# Schematics.net
KiCad netlist of a schematic drawn in Altium Designer
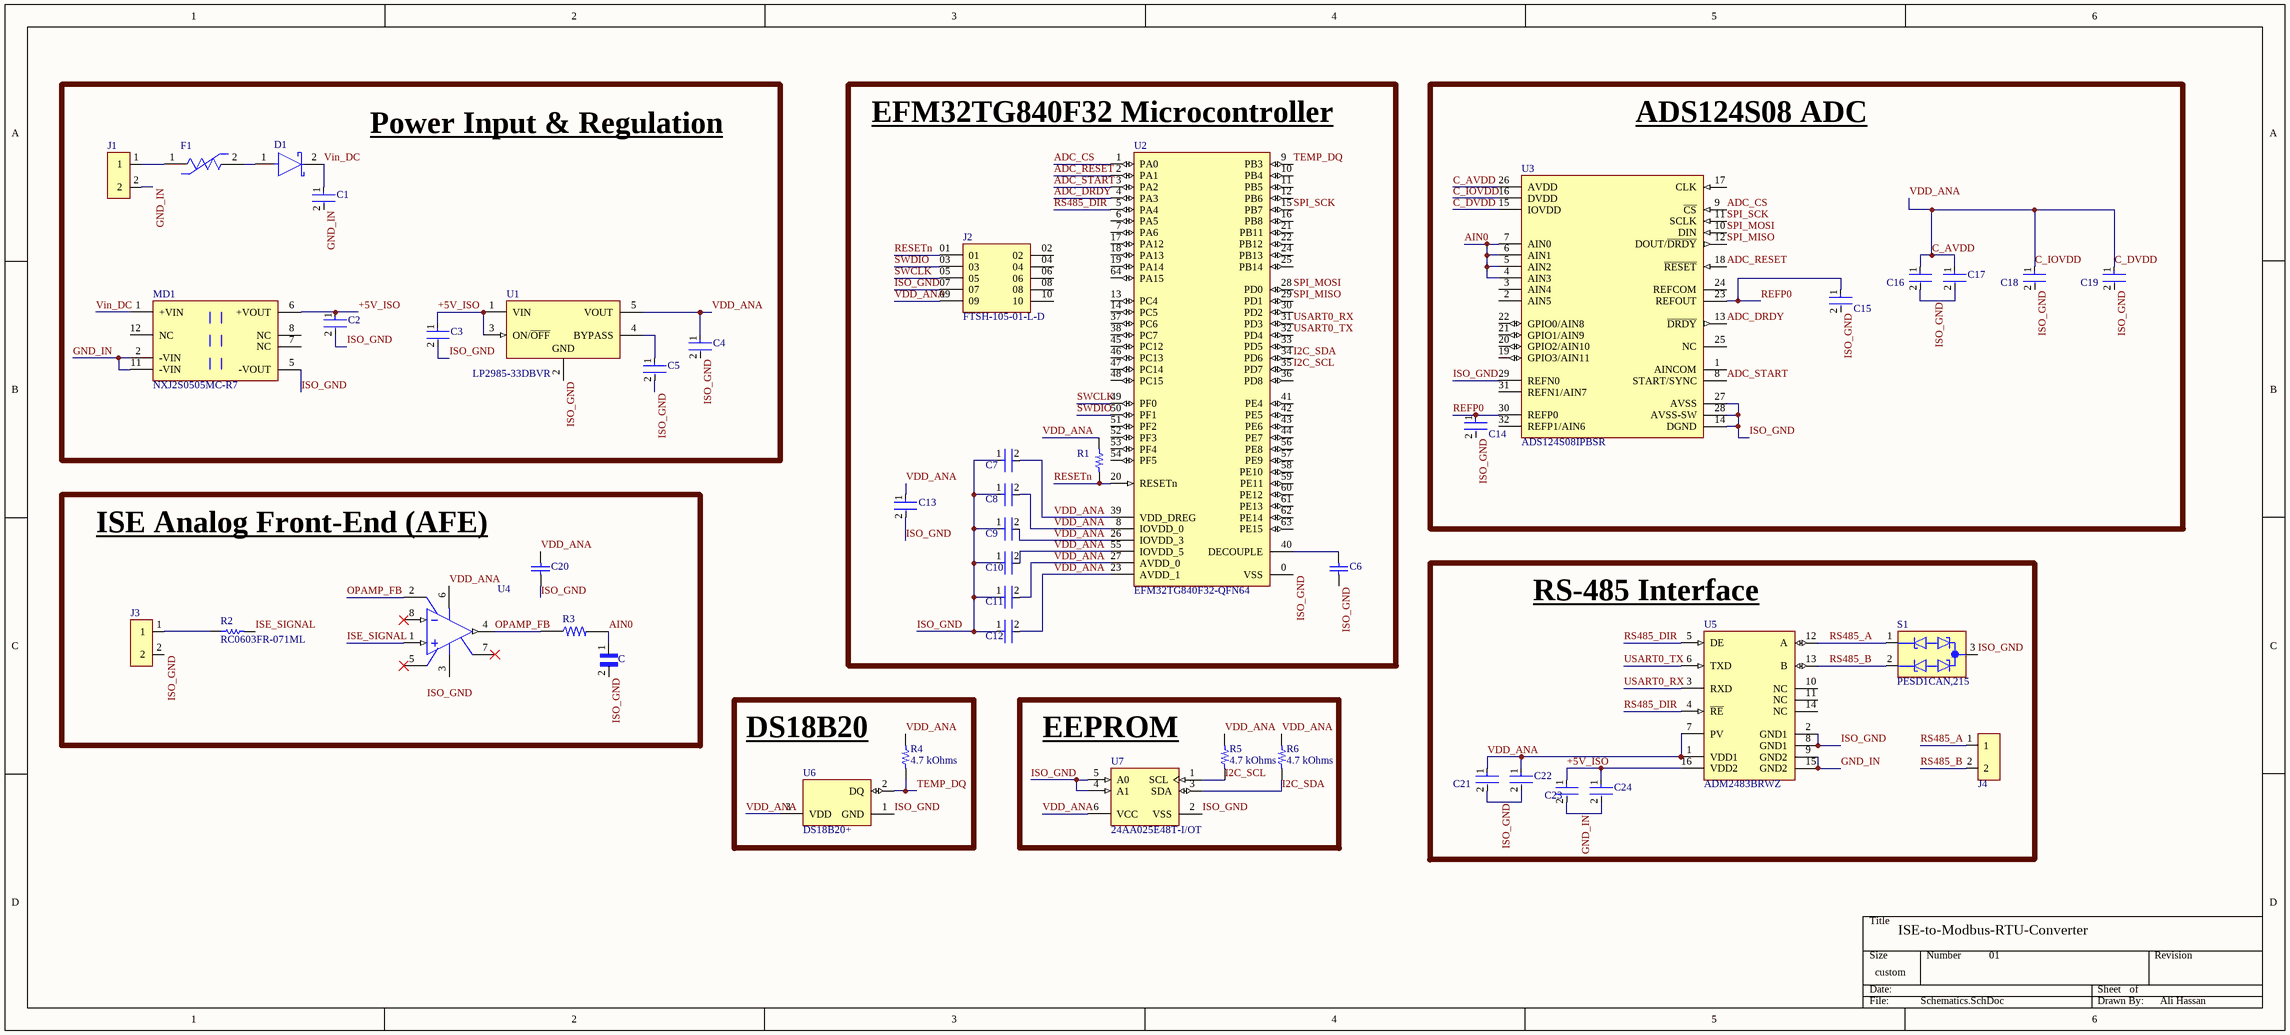
[diagram p0: Schematics.SchDoc]

(export (version "E")
  (design (tool "Eeschema 10.0.6"))
  (components
    (comp (ref "C")
      (value "CL10B104KO8NNNC")
      (footprint "CAPC1608X90N")
      (description "0.1ÂµF Â±10% 16V Ceramic Capacitor X7R 0603 _1608 Metric_")
      (fields (field (name "MF") "Samsung Electro-Mechanics"))
      (libsource (lib "CL10B104KO8NNNC") (part "CL10B104KO8NNNC"))
    )
    (comp (ref "C1")
      (value "GRM188R60J106ME47D")
      (footprint "FP-GRM188-0_1-e0_2_0_55-IPC_A")
      (description "Chip Multilayer Ceramic Capacitors for General Purpose, 0603, 10uF, X5R, 15%, 20%, 6.3V")
      (fields (field (name "VOLTAGE") "6.3V") (field (name "TOLERANCE") "20%"))
      (libsource (lib "Altium Content Vault") (part "02cd4be3c70576c341d710602a673aa"))
    )
    (comp (ref "C2")
      (value "GRM188R60J106ME47D")
      (footprint "FP-GRM188-0_1-e0_2_0_55-IPC_A")
      (description "Chip Multilayer Ceramic Capacitors for General Purpose, 0603, 10uF, X5R, 15%, 20%, 6.3V")
      (fields (field (name "VOLTAGE") "6.3V") (field (name "TOLERANCE") "20%"))
      (libsource (lib "Altium Content Vault") (part "02cd4be3c70576c341d710602a673aa"))
    )
    (comp (ref "C3")
      (value "GRM188R60J106ME47D")
      (footprint "FP-GRM188-0_1-e0_2_0_55-IPC_A")
      (description "Chip Multilayer Ceramic Capacitors for General Purpose, 0603, 10uF, X5R, 15%, 20%, 6.3V")
      (fields (field (name "VOLTAGE") "6.3V") (field (name "TOLERANCE") "20%"))
      (libsource (lib "Altium Content Vault") (part "02cd4be3c70576c341d710602a673aa"))
    )
    (comp (ref "C4")
      (value "GRM188R60J106ME47D")
      (footprint "FP-GRM188-0_1-e0_2_0_55-IPC_A")
      (description "Chip Multilayer Ceramic Capacitors for General Purpose, 0603, 10uF, X5R, 15%, 20%, 6.3V")
      (fields (field (name "VOLTAGE") "6.3V") (field (name "TOLERANCE") "20%"))
      (libsource (lib "Altium Content Vault") (part "02cd4be3c70576c341d710602a673aa"))
    )
    (comp (ref "C5")
      (value "GRM188R60J106ME47D")
      (footprint "FP-GRM188-0_1-e0_2_0_55-IPC_A")
      (description "Chip Multilayer Ceramic Capacitors for General Purpose, 0603, 10uF, X5R, 15%, 20%, 6.3V")
      (fields (field (name "VOLTAGE") "6.3V") (field (name "TOLERANCE") "20%"))
      (libsource (lib "Altium Content Vault") (part "02cd4be3c70576c341d710602a673aa"))
    )
    (comp (ref "C6")
      (value "C0805C105K4PACTU")
      (footprint "CAPC2013X145X50LL20T25")
      (fields (field (name "MANUFACTURER") "Kemet"))
      (libsource (lib "Altium Content Vault") (part "CAP"))
    )
    (comp (ref "C7")
      (value "C1005X7R1H104K050BB")
      (footprint "FP-C1005-050-0_05-IPC_C")
      (description "Multilayer Ceramic Capacitors 100nF ±10% 50V X7R SMD 0402")
      (fields (field (name "VOLTAGE") "50V") (field (name "TOLERANCE") "10%"))
      (libsource (lib "Altium Content Vault") (part "b4654b650e69147ec39a6b967a45e02"))
    )
    (comp (ref "C8")
      (value "C1005X7R1H104K050BB")
      (footprint "FP-C1005-050-0_05-IPC_C")
      (description "Multilayer Ceramic Capacitors 100nF ±10% 50V X7R SMD 0402")
      (fields (field (name "VOLTAGE") "50V") (field (name "TOLERANCE") "10%"))
      (libsource (lib "Altium Content Vault") (part "b4654b650e69147ec39a6b967a45e02"))
    )
    (comp (ref "C9")
      (value "C1005X7R1H104K050BB")
      (footprint "FP-C1005-050-0_05-IPC_C")
      (description "Multilayer Ceramic Capacitors 100nF ±10% 50V X7R SMD 0402")
      (fields (field (name "VOLTAGE") "50V") (field (name "TOLERANCE") "10%"))
      (libsource (lib "Altium Content Vault") (part "b4654b650e69147ec39a6b967a45e02"))
    )
    (comp (ref "C10")
      (value "C1005X7R1H104K050BB")
      (footprint "FP-C1005-050-0_05-IPC_C")
      (description "Multilayer Ceramic Capacitors 100nF ±10% 50V X7R SMD 0402")
      (fields (field (name "VOLTAGE") "50V") (field (name "TOLERANCE") "10%"))
      (libsource (lib "Altium Content Vault") (part "b4654b650e69147ec39a6b967a45e02"))
    )
    (comp (ref "C11")
      (value "C1005X7R1H104K050BB")
      (footprint "FP-C1005-050-0_05-IPC_C")
      (description "Multilayer Ceramic Capacitors 100nF ±10% 50V X7R SMD 0402")
      (fields (field (name "VOLTAGE") "50V") (field (name "TOLERANCE") "10%"))
      (libsource (lib "Altium Content Vault") (part "b4654b650e69147ec39a6b967a45e02"))
    )
    (comp (ref "C12")
      (value "C1005X7R1H104K050BB")
      (footprint "FP-C1005-050-0_05-IPC_C")
      (description "Multilayer Ceramic Capacitors 100nF ±10% 50V X7R SMD 0402")
      (fields (field (name "VOLTAGE") "50V") (field (name "TOLERANCE") "10%"))
      (libsource (lib "Altium Content Vault") (part "b4654b650e69147ec39a6b967a45e02"))
    )
    (comp (ref "C13")
      (value "GRM188R60J106ME47D")
      (footprint "FP-GRM188-0_1-e0_2_0_55-IPC_A")
      (description "Chip Multilayer Ceramic Capacitors for General Purpose, 0603, 10uF, X5R, 15%, 20%, 6.3V")
      (fields (field (name "VOLTAGE") "6.3V") (field (name "TOLERANCE") "20%"))
      (libsource (lib "Altium Content Vault") (part "02cd4be3c70576c341d710602a673aa"))
    )
    (comp (ref "C14")
      (value "C1005X7R1H104K050BB")
      (footprint "FP-C1005-050-0_05-IPC_C")
      (description "Multilayer Ceramic Capacitors 100nF ±10% 50V X7R SMD 0402")
      (fields (field (name "VOLTAGE") "50V") (field (name "TOLERANCE") "10%"))
      (libsource (lib "Altium Content Vault") (part "b4654b650e69147ec39a6b967a45e02"))
    )
    (comp (ref "C15")
      (value "C1005X7R1H104K050BB")
      (footprint "FP-C1005-050-0_05-IPC_C")
      (description "Multilayer Ceramic Capacitors 100nF ±10% 50V X7R SMD 0402")
      (fields (field (name "VOLTAGE") "50V") (field (name "TOLERANCE") "10%"))
      (libsource (lib "Altium Content Vault") (part "b4654b650e69147ec39a6b967a45e02"))
    )
    (comp (ref "C16")
      (value "C1005X7R1H104K050BB")
      (footprint "FP-C1005-050-0_05-IPC_C")
      (description "Multilayer Ceramic Capacitors 100nF ±10% 50V X7R SMD 0402")
      (fields (field (name "VOLTAGE") "50V") (field (name "TOLERANCE") "10%"))
      (libsource (lib "Altium Content Vault") (part "b4654b650e69147ec39a6b967a45e02"))
    )
    (comp (ref "C17")
      (value "GRM188R60J106ME47D")
      (footprint "FP-GRM188-0_1-e0_2_0_55-IPC_A")
      (description "Chip Multilayer Ceramic Capacitors for General Purpose, 0603, 10uF, X5R, 15%, 20%, 6.3V")
      (fields (field (name "VOLTAGE") "6.3V") (field (name "TOLERANCE") "20%"))
      (libsource (lib "Altium Content Vault") (part "02cd4be3c70576c341d710602a673aa"))
    )
    (comp (ref "C18")
      (value "C1005X7R1H104K050BB")
      (footprint "FP-C1005-050-0_05-IPC_C")
      (description "Multilayer Ceramic Capacitors 100nF ±10% 50V X7R SMD 0402")
      (fields (field (name "VOLTAGE") "50V") (field (name "TOLERANCE") "10%"))
      (libsource (lib "Altium Content Vault") (part "b4654b650e69147ec39a6b967a45e02"))
    )
    (comp (ref "C19")
      (value "C1005X7R1H104K050BB")
      (footprint "FP-C1005-050-0_05-IPC_C")
      (description "Multilayer Ceramic Capacitors 100nF ±10% 50V X7R SMD 0402")
      (fields (field (name "VOLTAGE") "50V") (field (name "TOLERANCE") "10%"))
      (libsource (lib "Altium Content Vault") (part "b4654b650e69147ec39a6b967a45e02"))
    )
    (comp (ref "C20")
      (value "GRM188R71C104KA01D")
      (footprint "MURA-0603_H_0.9_M")
      (description "CAP, Ceramic, 0.1 uF, 10%, 16 V, 0603, RoHS, Tape and Reel")
      (fields (field (name "MANUFACTURER") "Murata") (field (name "TOLERANCE") "10%"))
      (libsource (lib "Altium Content Vault") (part "CAP-NP-2"))
    )
    (comp (ref "C21")
      (value "C1005X7R1H104K050BB")
      (footprint "FP-C1005-050-0_05-IPC_C")
      (description "Multilayer Ceramic Capacitors 100nF ±10% 50V X7R SMD 0402")
      (fields (field (name "VOLTAGE") "50V") (field (name "TOLERANCE") "10%"))
      (libsource (lib "Altium Content Vault") (part "b4654b650e69147ec39a6b967a45e02"))
    )
    (comp (ref "C22")
      (value "GRM188R60J106ME47D")
      (footprint "FP-GRM188-0_1-e0_2_0_55-IPC_A")
      (description "Chip Multilayer Ceramic Capacitors for General Purpose, 0603, 10uF, X5R, 15%, 20%, 6.3V")
      (fields (field (name "VOLTAGE") "6.3V") (field (name "TOLERANCE") "20%"))
      (libsource (lib "Altium Content Vault") (part "02cd4be3c70576c341d710602a673aa"))
    )
    (comp (ref "C23")
      (value "C1005X7R1H104K050BB")
      (footprint "FP-C1005-050-0_05-IPC_C")
      (description "Multilayer Ceramic Capacitors 100nF ±10% 50V X7R SMD 0402")
      (fields (field (name "VOLTAGE") "50V") (field (name "TOLERANCE") "10%"))
      (libsource (lib "Altium Content Vault") (part "b4654b650e69147ec39a6b967a45e02"))
    )
    (comp (ref "C24")
      (value "GRM188R60J106ME47D")
      (footprint "FP-GRM188-0_1-e0_2_0_55-IPC_A")
      (description "Chip Multilayer Ceramic Capacitors for General Purpose, 0603, 10uF, X5R, 15%, 20%, 6.3V")
      (fields (field (name "VOLTAGE") "6.3V") (field (name "TOLERANCE") "20%"))
      (libsource (lib "Altium Content Vault") (part "02cd4be3c70576c341d710602a673aa"))
    )
    (comp (ref "D1")
      (value "SS14")
      (footprint "FP-403AE-MFG")
      (description "DIODE SCHOTTKY 40V 1A SMA")
      (fields
        (field (name "MANUFACTURER") "ON Semiconductor")
        (field (name "OCTOPART") "https://octopart.com/ss14-on+semiconductor-29205033")
      )
      (libsource (lib "Altium Content Vault") (part "360ad2f4ac25a952324d13796385471"))
    )
    (comp (ref "F1")
      (value "1206L050YR")
      (footprint "FP-1206L050YR-MFG")
      (description "PTC RESET FUSE 6V 500MA 1206")
      (libsource (lib "Altium Content Vault") (part "fdf083d5f6389a9a1c4e51137f46658"))
    )
    (comp (ref "J1")
      (value "OSTTC020162")
      (footprint "OST_OSTTC020162")
      (description "2 Position Wire to Board Terminal Block Horizontal with Board 0.197 _5.00mm_ Through Hole")
      (fields (field (name "MF") "On Shore"))
      (libsource (lib "OSTTC020162") (part "OSTTC020162"))
    )
    (comp (ref "J2")
      (value "FTSH-105-01-L-D")
      (footprint "SAMTEC_FTSH-105-01-L-D")
      (fields (field (name "MF") "Samtec"))
      (libsource (lib "FTSH-105-01-L-D") (part "FTSH-105-01-L-D"))
    )
    (comp (ref "J3")
      (value "OSTTC020162")
      (footprint "OST_OSTTC020162")
      (description "2 Position Wire to Board Terminal Block Horizontal with Board 0.197 _5.00mm_ Through Hole")
      (fields (field (name "MF") "On Shore"))
      (libsource (lib "OSTTC020162") (part "OSTTC020162"))
    )
    (comp (ref "J4")
      (value "OSTTC020162")
      (footprint "OST_OSTTC020162")
      (description "2 Position Wire to Board Terminal Block Horizontal with Board 0.197 _5.00mm_ Through Hole")
      (fields (field (name "MF") "On Shore"))
      (libsource (lib "") (part "OSTTC020162_1"))
    )
    (comp (ref "MD1")
      (value "NXJ2S0505MC-R7")
      (footprint "FP-NXJ2SM-MFG")
      (description "DC DC CONVERTER 5V 2W")
      (libsource (lib "Altium Content Vault") (part "702c7546206b672000c29661061961a"))
    )
    (comp (ref "R1")
      (value "10 kOhms")
      (footprint "YAGEO RES 0603_1608")
      (description "RES SMD 10K OHM 1% 1/10W 0603")
      (fields (field (name "PART NUMBER") "AA0603FR-0710KL") (field (name "MANUFACTURER") "Yageo"))
      (libsource (lib "Celestial Altium Library - altium_library") (part "Resistor"))
    )
    (comp (ref "R2")
      (value "RC0603FR-071ML")
      (footprint "RESC1608X55X25LL10T15")
      (description "Chip Resistor, 1 MOhm, +/- 1%, 100 mW, -55 to 155 degC, 0603 (1608 Metric), RoHS, Tape and Reel")
      (fields (field (name "TOLERANCE") "20%"))
      (libsource (lib "Altium Content Vault") (part "RES-2"))
    )
    (comp (ref "R3")
      (value "RC0603FR-07100RL")
      (footprint "RESC1607X60N")
      (description "100 Ohms Â±1% 0.1W, 1/10W Chip Resistor 0603 (1608 Metric) Moisture Resistant Thick Film")
      (fields (field (name "MF") "Yageo"))
      (libsource (lib "RC0603FR-07100RL") (part "RC0603FR-07100RL"))
    )
    (comp (ref "R4")
      (value "4.7 kOhms")
      (footprint "YAGEO RES 0603_1608")
      (description "RES SMD 4.7K OHM 1% 1/10W 0603")
      (fields (field (name "PART NUMBER") "AC0603FR-074K7L") (field (name "MANUFACTURER") "Yageo"))
      (libsource (lib "Celestial Altium Library - altium_library") (part "Resistor"))
    )
    (comp (ref "R5")
      (value "4.7 kOhms")
      (footprint "YAGEO RES 0603_1608")
      (description "RES SMD 4.7K OHM 1% 1/10W 0603")
      (fields (field (name "PART NUMBER") "AC0603FR-074K7L") (field (name "MANUFACTURER") "Yageo"))
      (libsource (lib "Celestial Altium Library - altium_library") (part "Resistor"))
    )
    (comp (ref "R6")
      (value "4.7 kOhms")
      (footprint "YAGEO RES 0603_1608")
      (description "RES SMD 4.7K OHM 1% 1/10W 0603")
      (fields (field (name "PART NUMBER") "AC0603FR-074K7L") (field (name "MANUFACTURER") "Yageo"))
      (libsource (lib "Celestial Altium Library - altium_library") (part "Resistor"))
    )
    (comp (ref "S1")
      (value "PESD1CAN,215")
      (footprint "DIO_PESD1CAN,215")
      (description "70V Clamp 3A (8/20Âµs) Ipp Tvs Diode Surface Mount TO-236AB")
      (fields (field (name "MF") "Nexperia USA Inc."))
      (libsource (lib "PESD1CAN_215") (part "PESD1CAN,215"))
    )
    (comp (ref "U1")
      (value "LP2985-33DBVR")
      (footprint "DBV0005A_M")
      (fields (field (name "MANUFACTURER") "Texas Instruments"))
      (libsource (lib "Altium Content Vault") (part "TI-LP2985_A-10DBV5"))
    )
    (comp (ref "U2")
      (value "EFM32TG840F32-QFN64")
      (footprint "ENMR-QFN64_N")
      (fields (field (name "GENERIC PART NUMBER") "EFM32TG840"))
      (libsource (lib "Altium Content Vault") (part "ENMR-EFM32TG840-QFN64"))
    )
    (comp (ref "U3")
      (value "ADS124S08IPBSR")
      (footprint "FP-PBS0032A-MFG")
      (description "IC ADC 24BIT SIGMA-DELTA 32LQFP")
      (libsource (lib "Altium Content Vault") (part "ee4dd7a7cdd789a170874cc8d5a3975"))
    )
    (comp (ref "U4")
      (value "LMP7721MA/NOPB")
      (footprint "D0008A_M")
      (description "3 Femtoampere Input Bias Current Precision Amplifier, 8-pin Narrow SOIC, Pb-Free")
      (fields (field (name "MANUFACTURER") "Texas Instruments"))
      (libsource (lib "Altium Content Vault") (part "AMP-OPA-LMP7721-8"))
    )
    (comp (ref "U5")
      (value "ADM2483BRWZ")
      (footprint "ADI-ADM2483BRWZ-16_M")
      (fields (field (name "MANUFACTURER") "Analog Devices"))
      (libsource (lib "Altium Content Vault") (part "ADI-ADM2483BRWZ-16"))
    )
    (comp (ref "U6")
      (value "DS18B20+")
      (footprint "Q3+1")
      (libsource (lib "Altium Content Vault") (part "SEN-TEMP-DS1821-SIL3"))
    )
    (comp (ref "U7")
      (value "24AA025E48T-I/OT")
      (footprint "MCHP-SOT-23-OT6_L")
      (fields (field (name "MANUFACTURER") "Microchip"))
      (libsource (lib "Altium Content Vault") (part "MCHP-24AA025E48-SOT-23-6"))
    )
  )
  (nets
    (net (code "1") (name "/+5V_ISO") (class "Default")
      (node (ref "C2") (pin "1") (pinfunction "1_1") (pintype "passive"))
      (node (ref "C23") (pin "1") (pinfunction "1_1") (pintype "passive"))
      (node (ref "C24") (pin "1") (pinfunction "1_1") (pintype "passive"))
      (node (ref "C3") (pin "1") (pinfunction "1_1") (pintype "passive"))
      (node (ref "MD1") (pin "6") (pinfunction "+VOUT_6") (pintype "power_in"))
      (node (ref "U1") (pin "1") (pinfunction "VIN_1") (pintype "power_in"))
      (node (ref "U1") (pin "3") (pinfunction "ON/~{OFF}_3") (pintype "input"))
      (node (ref "U5") (pin "16") (pinfunction "VDD2_16") (pintype "power_in"))
    )
    (net (code "2") (name "/ADC_CS") (class "Default")
      (node (ref "U2") (pin "1") (pinfunction "PA0_1") (pintype "bidirectional"))
      (node (ref "U3") (pin "9") (pinfunction "~{CS}_9") (pintype "input"))
    )
    (net (code "3") (name "/ADC_DRDY") (class "Default")
      (node (ref "U2") (pin "4") (pinfunction "PA3_4") (pintype "bidirectional"))
      (node (ref "U3") (pin "13") (pinfunction "~{DRDY}_13") (pintype "output"))
    )
    (net (code "4") (name "/ADC_RESET") (class "Default")
      (node (ref "U2") (pin "2") (pinfunction "PA1_2") (pintype "bidirectional"))
      (node (ref "U3") (pin "18") (pinfunction "~{RESET}_18") (pintype "input"))
    )
    (net (code "5") (name "/ADC_START") (class "Default")
      (node (ref "U2") (pin "3") (pinfunction "PA2_3") (pintype "bidirectional"))
      (node (ref "U3") (pin "8") (pinfunction "START/SYNC_8") (pintype "passive"))
    )
    (net (code "6") (name "/AIN0") (class "Default")
      (node (ref "C") (pin "1") (pinfunction "1_1") (pintype "passive"))
      (node (ref "R3") (pin "2") (pinfunction "2_2") (pintype "passive"))
      (node (ref "U3") (pin "4") (pinfunction "AIN3_4") (pintype "passive"))
      (node (ref "U3") (pin "5") (pinfunction "AIN2_5") (pintype "passive"))
      (node (ref "U3") (pin "6") (pinfunction "AIN1_6") (pintype "passive"))
      (node (ref "U3") (pin "7") (pinfunction "AIN0_7") (pintype "passive"))
    )
    (net (code "7") (name "/C_AVDD") (class "Default")
      (node (ref "C10") (pin "2") (pinfunction "2_2") (pintype "passive"))
      (node (ref "C11") (pin "2") (pinfunction "2_2") (pintype "passive"))
      (node (ref "C12") (pin "2") (pinfunction "2_2") (pintype "passive"))
      (node (ref "C13") (pin "1") (pinfunction "1_1") (pintype "passive"))
      (node (ref "C16") (pin "1") (pinfunction "1_1") (pintype "passive"))
      (node (ref "C17") (pin "1") (pinfunction "1_1") (pintype "passive"))
      (node (ref "C18") (pin "1") (pinfunction "1_1") (pintype "passive"))
      (node (ref "C19") (pin "1") (pinfunction "1_1") (pintype "passive"))
      (node (ref "C20") (pin "2") (pinfunction "2_2") (pintype "passive"))
      (node (ref "C21") (pin "1") (pinfunction "1_1") (pintype "passive"))
      (node (ref "C22") (pin "1") (pinfunction "1_1") (pintype "passive"))
      (node (ref "C4") (pin "1") (pinfunction "1_1") (pintype "passive"))
      (node (ref "C7") (pin "2") (pinfunction "2_2") (pintype "passive"))
      (node (ref "C8") (pin "2") (pinfunction "2_2") (pintype "passive"))
      (node (ref "C9") (pin "2") (pinfunction "2_2") (pintype "passive"))
      (node (ref "J2") (pin "09") (pinfunction "09_09") (pintype "passive"))
      (node (ref "R1") (pin "2") (pinfunction "2_2") (pintype "passive"))
      (node (ref "R4") (pin "2") (pinfunction "2_2") (pintype "passive"))
      (node (ref "R5") (pin "2") (pinfunction "2_2") (pintype "passive"))
      (node (ref "R6") (pin "2") (pinfunction "2_2") (pintype "passive"))
      (node (ref "U1") (pin "5") (pinfunction "VOUT_5") (pintype "power_in"))
      (node (ref "U2") (pin "23") (pinfunction "AVDD_1_23") (pintype "power_in"))
      (node (ref "U2") (pin "26") (pinfunction "IOVDD_3_26") (pintype "power_in"))
      (node (ref "U2") (pin "27") (pinfunction "AVDD_0_27") (pintype "power_in"))
      (node (ref "U2") (pin "39") (pinfunction "VDD_DREG_39") (pintype "power_in"))
      (node (ref "U2") (pin "55") (pinfunction "IOVDD_5_55") (pintype "power_in"))
      (node (ref "U2") (pin "8") (pinfunction "IOVDD_0_8") (pintype "power_in"))
      (node (ref "U3") (pin "15") (pinfunction "IOVDD_15") (pintype "power_in"))
      (node (ref "U3") (pin "16") (pinfunction "DVDD_16") (pintype "power_in"))
      (node (ref "U3") (pin "26") (pinfunction "AVDD_26") (pintype "power_in"))
      (node (ref "U4") (pin "6") (pinfunction "V+_6") (pintype "power_in"))
      (node (ref "U5") (pin "1") (pinfunction "VDD1_1") (pintype "power_in"))
      (node (ref "U5") (pin "7") (pinfunction "PV_7") (pintype "power_in"))
      (node (ref "U6") (pin "3") (pinfunction "VDD_3") (pintype "power_in"))
      (node (ref "U7") (pin "6") (pinfunction "VCC_6") (pintype "power_in"))
    )
    (net (code "8") (name "/GND_IN") (class "Default")
      (node (ref "C1") (pin "2") (pinfunction "2_2") (pintype "passive"))
      (node (ref "C23") (pin "2") (pinfunction "2_2") (pintype "passive"))
      (node (ref "C24") (pin "2") (pinfunction "2_2") (pintype "passive"))
      (node (ref "J1") (pin "2") (pinfunction "2_2") (pintype "passive"))
      (node (ref "MD1") (pin "11") (pinfunction "-VIN_11") (pintype "power_in"))
      (node (ref "MD1") (pin "2") (pinfunction "-VIN_2") (pintype "power_in"))
      (node (ref "U5") (pin "15") (pinfunction "GND2_15") (pintype "power_in"))
      (node (ref "U5") (pin "9") (pinfunction "GND2_9") (pintype "power_in"))
    )
    (net (code "9") (name "/I2C_SCL") (class "Default")
      (node (ref "R5") (pin "1") (pinfunction "1_1") (pintype "passive"))
      (node (ref "U2") (pin "35") (pinfunction "PD7_35") (pintype "bidirectional"))
      (node (ref "U7") (pin "1") (pinfunction "SCL_1") (pintype "input"))
    )
    (net (code "10") (name "/I2C_SDA") (class "Default")
      (node (ref "R6") (pin "1") (pinfunction "1_1") (pintype "passive"))
      (node (ref "U2") (pin "34") (pinfunction "PD6_34") (pintype "bidirectional"))
      (node (ref "U7") (pin "3") (pinfunction "SDA_3") (pintype "bidirectional"))
    )
    (net (code "11") (name "/ISE_SIGNAL") (class "Default")
      (node (ref "R2") (pin "2") (pinfunction "2_2") (pintype "passive"))
      (node (ref "U4") (pin "1") (pinfunction "IN+_1") (pintype "input"))
    )
    (net (code "12") (name "/ISO_GND") (class "Default")
      (node (ref "C") (pin "2") (pinfunction "2_2") (pintype "passive"))
      (node (ref "C10") (pin "1") (pinfunction "1_1") (pintype "passive"))
      (node (ref "C11") (pin "1") (pinfunction "1_1") (pintype "passive"))
      (node (ref "C12") (pin "1") (pinfunction "1_1") (pintype "passive"))
      (node (ref "C13") (pin "2") (pinfunction "2_2") (pintype "passive"))
      (node (ref "C14") (pin "2") (pinfunction "2_2") (pintype "passive"))
      (node (ref "C15") (pin "2") (pinfunction "2_2") (pintype "passive"))
      (node (ref "C16") (pin "2") (pinfunction "2_2") (pintype "passive"))
      (node (ref "C17") (pin "2") (pinfunction "2_2") (pintype "passive"))
      (node (ref "C18") (pin "2") (pinfunction "2_2") (pintype "passive"))
      (node (ref "C19") (pin "2") (pinfunction "2_2") (pintype "passive"))
      (node (ref "C2") (pin "2") (pinfunction "2_2") (pintype "passive"))
      (node (ref "C20") (pin "1") (pinfunction "1_1") (pintype "passive"))
      (node (ref "C21") (pin "2") (pinfunction "2_2") (pintype "passive"))
      (node (ref "C22") (pin "2") (pinfunction "2_2") (pintype "passive"))
      (node (ref "C3") (pin "2") (pinfunction "2_2") (pintype "passive"))
      (node (ref "C4") (pin "2") (pinfunction "2_2") (pintype "passive"))
      (node (ref "C5") (pin "2") (pinfunction "2_2") (pintype "passive"))
      (node (ref "C6") (pin "1") (pinfunction "1_1") (pintype "passive"))
      (node (ref "C7") (pin "1") (pinfunction "1_1") (pintype "passive"))
      (node (ref "C8") (pin "1") (pinfunction "1_1") (pintype "passive"))
      (node (ref "C9") (pin "1") (pinfunction "1_1") (pintype "passive"))
      (node (ref "J2") (pin "07") (pinfunction "07_07") (pintype "passive"))
      (node (ref "J3") (pin "2") (pinfunction "2_2") (pintype "passive"))
      (node (ref "MD1") (pin "5") (pinfunction "-VOUT_5") (pintype "power_in"))
      (node (ref "S1") (pin "3") (pinfunction "CC_3") (pintype "passive"))
      (node (ref "U1") (pin "2") (pinfunction "GND_2") (pintype "power_in"))
      (node (ref "U2") (pin "0") (pinfunction "VSS_0") (pintype "power_in"))
      (node (ref "U3") (pin "14") (pinfunction "DGND_14") (pintype "power_in"))
      (node (ref "U3") (pin "27") (pinfunction "AVSS_27") (pintype "power_in"))
      (node (ref "U3") (pin "28") (pinfunction "AVSS-SW_28") (pintype "power_in"))
      (node (ref "U3") (pin "29") (pinfunction "REFN0_29") (pintype "passive"))
      (node (ref "U5") (pin "2") (pinfunction "GND1_2") (pintype "power_in"))
      (node (ref "U5") (pin "8") (pinfunction "GND1_8") (pintype "power_in"))
      (node (ref "U6") (pin "1") (pinfunction "GND_1") (pintype "power_in"))
      (node (ref "U7") (pin "2") (pinfunction "VSS_2") (pintype "power_in"))
      (node (ref "U7") (pin "4") (pinfunction "A1_4") (pintype "input"))
      (node (ref "U7") (pin "5") (pinfunction "A0_5") (pintype "input"))
    )
    (net (code "13") (name "/OPAMP_FB") (class "Default")
      (node (ref "R3") (pin "1") (pinfunction "1_1") (pintype "passive"))
      (node (ref "U4") (pin "2") (pinfunction "NC_2") (pintype "passive"))
      (node (ref "U4") (pin "4") (pinfunction "OUT_4") (pintype "output"))
    )
    (net (code "14") (name "/REFP0") (class "Default")
      (node (ref "C14") (pin "1") (pinfunction "1_1") (pintype "passive"))
      (node (ref "C15") (pin "1") (pinfunction "1_1") (pintype "passive"))
      (node (ref "U3") (pin "23") (pinfunction "REFOUT_23") (pintype "passive"))
      (node (ref "U3") (pin "30") (pinfunction "REFP0_30") (pintype "passive"))
    )
    (net (code "15") (name "/RESETn") (class "Default")
      (node (ref "J2") (pin "01") (pinfunction "01_01") (pintype "passive"))
      (node (ref "R1") (pin "1") (pinfunction "1_1") (pintype "passive"))
      (node (ref "U2") (pin "20") (pinfunction "RESETn_20") (pintype "input"))
    )
    (net (code "16") (name "/RS485_A") (class "Default")
      (node (ref "J4") (pin "1") (pinfunction "1_1") (pintype "passive"))
      (node (ref "S1") (pin "1") (pinfunction "C1_1") (pintype "passive"))
      (node (ref "U5") (pin "12") (pinfunction "A_12") (pintype "bidirectional"))
    )
    (net (code "17") (name "/RS485_B") (class "Default")
      (node (ref "J4") (pin "2") (pinfunction "2_2") (pintype "passive"))
      (node (ref "S1") (pin "2") (pinfunction "C2_2") (pintype "passive"))
      (node (ref "U5") (pin "13") (pinfunction "B_13") (pintype "bidirectional"))
    )
    (net (code "18") (name "/RS485_DIR") (class "Default")
      (node (ref "U2") (pin "5") (pinfunction "PA4_5") (pintype "bidirectional"))
      (node (ref "U5") (pin "4") (pinfunction "~{RE}_4") (pintype "input"))
      (node (ref "U5") (pin "5") (pinfunction "DE_5") (pintype "input"))
    )
    (net (code "19") (name "/SPI_MISO") (class "Default")
      (node (ref "U2") (pin "29") (pinfunction "PD1_29") (pintype "bidirectional"))
      (node (ref "U3") (pin "12") (pinfunction "DOUT/~{DRDY}_12") (pintype "output"))
    )
    (net (code "20") (name "/SPI_MOSI") (class "Default")
      (node (ref "U2") (pin "28") (pinfunction "PD0_28") (pintype "bidirectional"))
      (node (ref "U3") (pin "10") (pinfunction "DIN_10") (pintype "input"))
    )
    (net (code "21") (name "/SPI_SCK") (class "Default")
      (node (ref "U2") (pin "15") (pinfunction "PB7_15") (pintype "bidirectional"))
      (node (ref "U3") (pin "11") (pinfunction "SCLK_11") (pintype "input"))
    )
    (net (code "22") (name "/SWCLK") (class "Default")
      (node (ref "J2") (pin "05") (pinfunction "05_05") (pintype "passive"))
      (node (ref "U2") (pin "49") (pinfunction "PF0_49") (pintype "bidirectional"))
    )
    (net (code "23") (name "/SWDIO") (class "Default")
      (node (ref "J2") (pin "03") (pinfunction "03_03") (pintype "passive"))
      (node (ref "U2") (pin "50") (pinfunction "PF1_50") (pintype "bidirectional"))
    )
    (net (code "24") (name "/TEMP_DQ") (class "Default")
      (node (ref "R4") (pin "1") (pinfunction "1_1") (pintype "passive"))
      (node (ref "U2") (pin "9") (pinfunction "PB3_9") (pintype "bidirectional"))
      (node (ref "U6") (pin "2") (pinfunction "DQ_2") (pintype "bidirectional"))
    )
    (net (code "25") (name "/USART0_RX") (class "Default")
      (node (ref "U2") (pin "31") (pinfunction "PD3_31") (pintype "bidirectional"))
      (node (ref "U5") (pin "3") (pinfunction "RXD_3") (pintype "tri_state"))
    )
    (net (code "26") (name "/USART0_TX") (class "Default")
      (node (ref "U2") (pin "32") (pinfunction "PD4_32") (pintype "bidirectional"))
      (node (ref "U5") (pin "6") (pinfunction "TXD_6") (pintype "input"))
    )
    (net (code "27") (name "/Vin_DC") (class "Default")
      (node (ref "C1") (pin "1") (pinfunction "1_1") (pintype "passive"))
      (node (ref "D1") (pin "2") (pinfunction "C_2") (pintype "passive"))
      (node (ref "MD1") (pin "1") (pinfunction "+VIN_1") (pintype "power_in"))
    )
    (net (code "28") (name "Net-(D1-A)") (class "Default")
      (node (ref "D1") (pin "1") (pinfunction "A_1") (pintype "passive"))
      (node (ref "F1") (pin "2") (pinfunction "2_2") (pintype "passive"))
    )
    (net (code "29") (name "Net-(F1-Pad1)") (class "Default")
      (node (ref "F1") (pin "1") (pinfunction "1_1") (pintype "passive"))
      (node (ref "J1") (pin "1") (pinfunction "1_1") (pintype "passive"))
    )
    (net (code "30") (name "Net-(J3-Pad1)") (class "Default")
      (node (ref "J3") (pin "1") (pinfunction "1_1") (pintype "passive"))
      (node (ref "R2") (pin "1") (pinfunction "1_1") (pintype "passive"))
    )
    (net (code "31") (name "Net-(U1-BYPASS)") (class "Default")
      (node (ref "C5") (pin "1") (pinfunction "1_1") (pintype "passive"))
      (node (ref "U1") (pin "4") (pinfunction "BYPASS_4") (pintype "passive"))
    )
    (net (code "32") (name "Net-(U2-DECOUPLE)") (class "Default")
      (node (ref "C6") (pin "2") (pinfunction "2_2") (pintype "passive"))
      (node (ref "U2") (pin "40") (pinfunction "DECOUPLE_40") (pintype "passive"))
    )
    (net (code "33") (name "unconnected-(J2-Pad02)") (class "Default")
      (node (ref "J2") (pin "02") (pinfunction "02_02") (pintype "passive"))
    )
    (net (code "34") (name "unconnected-(J2-Pad04)") (class "Default")
      (node (ref "J2") (pin "04") (pinfunction "04_04") (pintype "passive"))
    )
    (net (code "35") (name "unconnected-(J2-Pad06)") (class "Default")
      (node (ref "J2") (pin "06") (pinfunction "06_06") (pintype "passive"))
    )
    (net (code "36") (name "unconnected-(J2-Pad08)") (class "Default")
      (node (ref "J2") (pin "08") (pinfunction "08_08") (pintype "passive"))
    )
    (net (code "37") (name "unconnected-(J2-Pad10)") (class "Default")
      (node (ref "J2") (pin "10") (pinfunction "10_10") (pintype "passive"))
    )
    (net (code "38") (name "unconnected-(MD1-NC-Pad7)") (class "Default")
      (node (ref "MD1") (pin "7") (pinfunction "NC_7") (pintype "passive"))
    )
    (net (code "39") (name "unconnected-(MD1-NC-Pad8)") (class "Default")
      (node (ref "MD1") (pin "8") (pinfunction "NC_8") (pintype "passive"))
    )
    (net (code "40") (name "unconnected-(MD1-NC-Pad12)") (class "Default")
      (node (ref "MD1") (pin "12") (pinfunction "NC_12") (pintype "passive"))
    )
    (net (code "41") (name "unconnected-(U2-PA5-Pad6)") (class "Default")
      (node (ref "U2") (pin "6") (pinfunction "PA5_6") (pintype "bidirectional"))
    )
    (net (code "42") (name "unconnected-(U2-PA6-Pad7)") (class "Default")
      (node (ref "U2") (pin "7") (pinfunction "PA6_7") (pintype "bidirectional"))
    )
    (net (code "43") (name "unconnected-(U2-PA12-Pad17)") (class "Default")
      (node (ref "U2") (pin "17") (pinfunction "PA12_17") (pintype "bidirectional"))
    )
    (net (code "44") (name "unconnected-(U2-PA13-Pad18)") (class "Default")
      (node (ref "U2") (pin "18") (pinfunction "PA13_18") (pintype "bidirectional"))
    )
    (net (code "45") (name "unconnected-(U2-PA14-Pad19)") (class "Default")
      (node (ref "U2") (pin "19") (pinfunction "PA14_19") (pintype "bidirectional"))
    )
    (net (code "46") (name "unconnected-(U2-PA15-Pad64)") (class "Default")
      (node (ref "U2") (pin "64") (pinfunction "PA15_64") (pintype "bidirectional"))
    )
    (net (code "47") (name "unconnected-(U2-PB4-Pad10)") (class "Default")
      (node (ref "U2") (pin "10") (pinfunction "PB4_10") (pintype "bidirectional"))
    )
    (net (code "48") (name "unconnected-(U2-PB5-Pad11)") (class "Default")
      (node (ref "U2") (pin "11") (pinfunction "PB5_11") (pintype "bidirectional"))
    )
    (net (code "49") (name "unconnected-(U2-PB6-Pad12)") (class "Default")
      (node (ref "U2") (pin "12") (pinfunction "PB6_12") (pintype "bidirectional"))
    )
    (net (code "50") (name "unconnected-(U2-PB8-Pad16)") (class "Default")
      (node (ref "U2") (pin "16") (pinfunction "PB8_16") (pintype "bidirectional"))
    )
    (net (code "51") (name "unconnected-(U2-PB11-Pad21)") (class "Default")
      (node (ref "U2") (pin "21") (pinfunction "PB11_21") (pintype "bidirectional"))
    )
    (net (code "52") (name "unconnected-(U2-PB12-Pad22)") (class "Default")
      (node (ref "U2") (pin "22") (pinfunction "PB12_22") (pintype "bidirectional"))
    )
    (net (code "53") (name "unconnected-(U2-PB13-Pad24)") (class "Default")
      (node (ref "U2") (pin "24") (pinfunction "PB13_24") (pintype "bidirectional"))
    )
    (net (code "54") (name "unconnected-(U2-PB14-Pad25)") (class "Default")
      (node (ref "U2") (pin "25") (pinfunction "PB14_25") (pintype "bidirectional"))
    )
    (net (code "55") (name "unconnected-(U2-PC4-Pad13)") (class "Default")
      (node (ref "U2") (pin "13") (pinfunction "PC4_13") (pintype "bidirectional"))
    )
    (net (code "56") (name "unconnected-(U2-PC5-Pad14)") (class "Default")
      (node (ref "U2") (pin "14") (pinfunction "PC5_14") (pintype "bidirectional"))
    )
    (net (code "57") (name "unconnected-(U2-PC6-Pad37)") (class "Default")
      (node (ref "U2") (pin "37") (pinfunction "PC6_37") (pintype "bidirectional"))
    )
    (net (code "58") (name "unconnected-(U2-PC7-Pad38)") (class "Default")
      (node (ref "U2") (pin "38") (pinfunction "PC7_38") (pintype "bidirectional"))
    )
    (net (code "59") (name "unconnected-(U2-PC12-Pad45)") (class "Default")
      (node (ref "U2") (pin "45") (pinfunction "PC12_45") (pintype "bidirectional"))
    )
    (net (code "60") (name "unconnected-(U2-PC13-Pad46)") (class "Default")
      (node (ref "U2") (pin "46") (pinfunction "PC13_46") (pintype "bidirectional"))
    )
    (net (code "61") (name "unconnected-(U2-PC14-Pad47)") (class "Default")
      (node (ref "U2") (pin "47") (pinfunction "PC14_47") (pintype "bidirectional"))
    )
    (net (code "62") (name "unconnected-(U2-PC15-Pad48)") (class "Default")
      (node (ref "U2") (pin "48") (pinfunction "PC15_48") (pintype "bidirectional"))
    )
    (net (code "63") (name "unconnected-(U2-PD2-Pad30)") (class "Default")
      (node (ref "U2") (pin "30") (pinfunction "PD2_30") (pintype "bidirectional"))
    )
    (net (code "64") (name "unconnected-(U2-PD5-Pad33)") (class "Default")
      (node (ref "U2") (pin "33") (pinfunction "PD5_33") (pintype "bidirectional"))
    )
    (net (code "65") (name "unconnected-(U2-PD8-Pad36)") (class "Default")
      (node (ref "U2") (pin "36") (pinfunction "PD8_36") (pintype "bidirectional"))
    )
    (net (code "66") (name "unconnected-(U2-PE4-Pad41)") (class "Default")
      (node (ref "U2") (pin "41") (pinfunction "PE4_41") (pintype "bidirectional"))
    )
    (net (code "67") (name "unconnected-(U2-PE5-Pad42)") (class "Default")
      (node (ref "U2") (pin "42") (pinfunction "PE5_42") (pintype "bidirectional"))
    )
    (net (code "68") (name "unconnected-(U2-PE6-Pad43)") (class "Default")
      (node (ref "U2") (pin "43") (pinfunction "PE6_43") (pintype "bidirectional"))
    )
    (net (code "69") (name "unconnected-(U2-PE7-Pad44)") (class "Default")
      (node (ref "U2") (pin "44") (pinfunction "PE7_44") (pintype "bidirectional"))
    )
    (net (code "70") (name "unconnected-(U2-PE8-Pad56)") (class "Default")
      (node (ref "U2") (pin "56") (pinfunction "PE8_56") (pintype "bidirectional"))
    )
    (net (code "71") (name "unconnected-(U2-PE9-Pad57)") (class "Default")
      (node (ref "U2") (pin "57") (pinfunction "PE9_57") (pintype "bidirectional"))
    )
    (net (code "72") (name "unconnected-(U2-PE10-Pad58)") (class "Default")
      (node (ref "U2") (pin "58") (pinfunction "PE10_58") (pintype "bidirectional"))
    )
    (net (code "73") (name "unconnected-(U2-PE11-Pad59)") (class "Default")
      (node (ref "U2") (pin "59") (pinfunction "PE11_59") (pintype "bidirectional"))
    )
    (net (code "74") (name "unconnected-(U2-PE12-Pad60)") (class "Default")
      (node (ref "U2") (pin "60") (pinfunction "PE12_60") (pintype "bidirectional"))
    )
    (net (code "75") (name "unconnected-(U2-PE13-Pad61)") (class "Default")
      (node (ref "U2") (pin "61") (pinfunction "PE13_61") (pintype "bidirectional"))
    )
    (net (code "76") (name "unconnected-(U2-PE14-Pad62)") (class "Default")
      (node (ref "U2") (pin "62") (pinfunction "PE14_62") (pintype "bidirectional"))
    )
    (net (code "77") (name "unconnected-(U2-PE15-Pad63)") (class "Default")
      (node (ref "U2") (pin "63") (pinfunction "PE15_63") (pintype "bidirectional"))
    )
    (net (code "78") (name "unconnected-(U2-PF2-Pad51)") (class "Default")
      (node (ref "U2") (pin "51") (pinfunction "PF2_51") (pintype "bidirectional"))
    )
    (net (code "79") (name "unconnected-(U2-PF3-Pad52)") (class "Default")
      (node (ref "U2") (pin "52") (pinfunction "PF3_52") (pintype "bidirectional"))
    )
    (net (code "80") (name "unconnected-(U2-PF4-Pad53)") (class "Default")
      (node (ref "U2") (pin "53") (pinfunction "PF4_53") (pintype "bidirectional"))
    )
    (net (code "81") (name "unconnected-(U2-PF5-Pad54)") (class "Default")
      (node (ref "U2") (pin "54") (pinfunction "PF5_54") (pintype "bidirectional"))
    )
    (net (code "82") (name "unconnected-(U3-AIN4-Pad3)") (class "Default")
      (node (ref "U3") (pin "3") (pinfunction "AIN4_3") (pintype "passive"))
    )
    (net (code "83") (name "unconnected-(U3-AIN5-Pad2)") (class "Default")
      (node (ref "U3") (pin "2") (pinfunction "AIN5_2") (pintype "passive"))
    )
    (net (code "84") (name "unconnected-(U3-AINCOM-Pad1)") (class "Default")
      (node (ref "U3") (pin "1") (pinfunction "AINCOM_1") (pintype "passive"))
    )
    (net (code "85") (name "unconnected-(U3-CLK-Pad17)") (class "Default")
      (node (ref "U3") (pin "17") (pinfunction "CLK_17") (pintype "input"))
    )
    (net (code "86") (name "unconnected-(U3-GPIO0{slash}AIN8-Pad22)") (class "Default")
      (node (ref "U3") (pin "22") (pinfunction "GPIO0/AIN8_22") (pintype "bidirectional"))
    )
    (net (code "87") (name "unconnected-(U3-GPIO1{slash}AIN9-Pad21)") (class "Default")
      (node (ref "U3") (pin "21") (pinfunction "GPIO1/AIN9_21") (pintype "bidirectional"))
    )
    (net (code "88") (name "unconnected-(U3-GPIO2{slash}AIN10-Pad20)") (class "Default")
      (node (ref "U3") (pin "20") (pinfunction "GPIO2/AIN10_20") (pintype "bidirectional"))
    )
    (net (code "89") (name "unconnected-(U3-GPIO3{slash}AIN11-Pad19)") (class "Default")
      (node (ref "U3") (pin "19") (pinfunction "GPIO3/AIN11_19") (pintype "bidirectional"))
    )
    (net (code "90") (name "unconnected-(U3-NC-Pad25)") (class "Default")
      (node (ref "U3") (pin "25") (pinfunction "NC_25") (pintype "passive"))
    )
    (net (code "91") (name "unconnected-(U3-REFCOM-Pad24)") (class "Default")
      (node (ref "U3") (pin "24") (pinfunction "REFCOM_24") (pintype "passive"))
    )
    (net (code "92") (name "unconnected-(U3-REFN1{slash}AIN7-Pad31)") (class "Default")
      (node (ref "U3") (pin "31") (pinfunction "REFN1/AIN7_31") (pintype "passive"))
    )
    (net (code "93") (name "unconnected-(U3-REFP1{slash}AIN6-Pad32)") (class "Default")
      (node (ref "U3") (pin "32") (pinfunction "REFP1/AIN6_32") (pintype "passive"))
    )
    (net (code "94") (name "unconnected-(U4-IN--Pad8)") (class "Default")
      (node (ref "U4") (pin "8") (pinfunction "IN-_8") (pintype "input+no_connect"))
    )
    (net (code "95") (name "unconnected-(U4-NC-Pad5)") (class "Default")
      (node (ref "U4") (pin "5") (pinfunction "NC_5") (pintype "passive+no_connect"))
    )
    (net (code "96") (name "unconnected-(U4-NC-Pad7)") (class "Default")
      (node (ref "U4") (pin "7") (pinfunction "NC_7") (pintype "passive+no_connect"))
    )
    (net (code "97") (name "unconnected-(U4-V--Pad3)") (class "Default")
      (node (ref "U4") (pin "3") (pinfunction "V-_3") (pintype "power_in"))
    )
    (net (code "98") (name "unconnected-(U5-NC-Pad10)") (class "Default")
      (node (ref "U5") (pin "10") (pinfunction "NC_10") (pintype "passive"))
    )
    (net (code "99") (name "unconnected-(U5-NC-Pad11)") (class "Default")
      (node (ref "U5") (pin "11") (pinfunction "NC_11") (pintype "passive"))
    )
    (net (code "100") (name "unconnected-(U5-NC-Pad14)") (class "Default")
      (node (ref "U5") (pin "14") (pinfunction "NC_14") (pintype "passive"))
    )
  )
)
